# RS485_ADM3485.net
KiCad netlist of a schematic drawn in Altium Designer
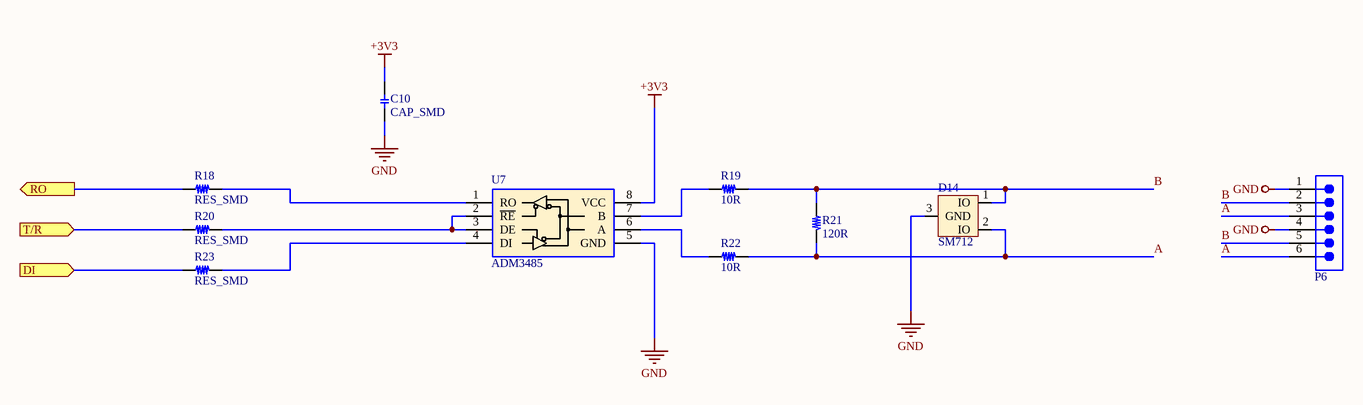
[diagram p0: RS485_ADM3485.SchDoc]

(export (version "E")
  (design (tool "Eeschema 10.0.6"))
  (components
    (comp (ref "C10")
      (value "CAP_SMD")
      (footprint "C 0603")
      (libsource (lib "radmehr_library") (part "CAP_SMD"))
    )
    (comp (ref "D14")
      (value "SM712")
      (footprint "SOT-23_3_D")
      (libsource (lib "radmehr_library") (part "SM712"))
    )
    (comp (ref "P6")
      (value "691321300006")
      (footprint "691321300006")
      (description "WR-TBL Series 321 Vertical PCB Header, Through Hole, pitch 3.81mm, 6p")
      (fields (field (name "MANUFACTURER") "Wurth Elektronik"))
      (libsource (lib "Altium_WR-TBL (rev22a)") (part "691321300006"))
    )
    (comp (ref "R18")
      (value "RES_SMD")
      (footprint "R 0603")
      (libsource (lib "radmehr_library") (part "RES_SMD"))
    )
    (comp (ref "R19")
      (value "10R")
      (footprint "R 1206")
      (description "RES_SMD")
      (libsource (lib "radmehr_library") (part "RES_SMD"))
    )
    (comp (ref "R20")
      (value "RES_SMD")
      (footprint "R 0603")
      (libsource (lib "radmehr_library") (part "RES_SMD"))
    )
    (comp (ref "R21")
      (value "120R")
      (footprint "R 1206")
      (description "RES_SMD")
      (libsource (lib "radmehr_library") (part "RES_SMD"))
    )
    (comp (ref "R22")
      (value "10R")
      (footprint "R 1206")
      (description "RES_SMD")
      (libsource (lib "radmehr_library") (part "RES_SMD"))
    )
    (comp (ref "R23")
      (value "RES_SMD")
      (footprint "R 0603")
      (libsource (lib "radmehr_library") (part "RES_SMD"))
    )
    (comp (ref "U7")
      (value "ADM3485")
      (footprint "SOIC-8")
      (libsource (lib "radmehr_library") (part "ADM3485"))
    )
  )
  (nets
    (net (code "1") (name "+3V3") (class "Default")
      (node (ref "C10") (pin "2") (pinfunction "2_2") (pintype "passive"))
      (node (ref "U7") (pin "8") (pinfunction "VCC_8") (pintype "passive"))
    )
    (net (code "2") (name "/A") (class "Default")
      (node (ref "D14") (pin "2") (pinfunction "IO_2") (pintype "passive"))
      (node (ref "P6") (pin "3") (pinfunction "3_3") (pintype "passive"))
      (node (ref "P6") (pin "6") (pinfunction "6_6") (pintype "passive"))
      (node (ref "R21") (pin "2") (pinfunction "2_2") (pintype "passive"))
      (node (ref "R22") (pin "2") (pinfunction "2_2") (pintype "passive"))
    )
    (net (code "3") (name "/B") (class "Default")
      (node (ref "D14") (pin "1") (pinfunction "IO_1") (pintype "passive"))
      (node (ref "P6") (pin "2") (pinfunction "2_2") (pintype "passive"))
      (node (ref "P6") (pin "5") (pinfunction "5_5") (pintype "passive"))
      (node (ref "R19") (pin "2") (pinfunction "2_2") (pintype "passive"))
      (node (ref "R21") (pin "1") (pinfunction "1_1") (pintype "passive"))
    )
    (net (code "4") (name "/DI") (class "Default")
      (node (ref "R23") (pin "1") (pinfunction "1_1") (pintype "passive"))
    )
    (net (code "5") (name "/RO") (class "Default")
      (node (ref "R18") (pin "1") (pinfunction "1_1") (pintype "passive"))
    )
    (net (code "6") (name "/T{slash}R") (class "Default")
      (node (ref "R20") (pin "1") (pinfunction "1_1") (pintype "passive"))
    )
    (net (code "7") (name "GND") (class "Default")
      (node (ref "C10") (pin "1") (pinfunction "1_1") (pintype "passive"))
      (node (ref "D14") (pin "3") (pinfunction "GND_3") (pintype "passive"))
      (node (ref "P6") (pin "1") (pinfunction "1_1") (pintype "passive"))
      (node (ref "P6") (pin "4") (pinfunction "4_4") (pintype "passive"))
      (node (ref "U7") (pin "5") (pinfunction "GND_5") (pintype "passive"))
    )
    (net (code "8") (name "Net-(U7-A)") (class "Default")
      (node (ref "R22") (pin "1") (pinfunction "1_1") (pintype "passive"))
      (node (ref "U7") (pin "6") (pinfunction "A_6") (pintype "passive"))
    )
    (net (code "9") (name "Net-(U7-B)") (class "Default")
      (node (ref "R19") (pin "1") (pinfunction "1_1") (pintype "passive"))
      (node (ref "U7") (pin "7") (pinfunction "B_7") (pintype "passive"))
    )
    (net (code "10") (name "Net-(U7-DE)") (class "Default")
      (node (ref "R20") (pin "2") (pinfunction "2_2") (pintype "passive"))
      (node (ref "U7") (pin "2") (pinfunction "~{RE}_2") (pintype "passive"))
      (node (ref "U7") (pin "3") (pinfunction "DE_3") (pintype "passive"))
    )
    (net (code "11") (name "Net-(U7-DI)") (class "Default")
      (node (ref "R23") (pin "2") (pinfunction "2_2") (pintype "passive"))
      (node (ref "U7") (pin "4") (pinfunction "DI_4") (pintype "passive"))
    )
    (net (code "12") (name "Net-(U7-RO)") (class "Default")
      (node (ref "R18") (pin "2") (pinfunction "2_2") (pintype "passive"))
      (node (ref "U7") (pin "1") (pinfunction "RO_1") (pintype "passive"))
    )
  )
)
